# SCH_Attiny85_DevBoard_2023-10-31.net
KiCad netlist of a schematic drawn in EasyEDA
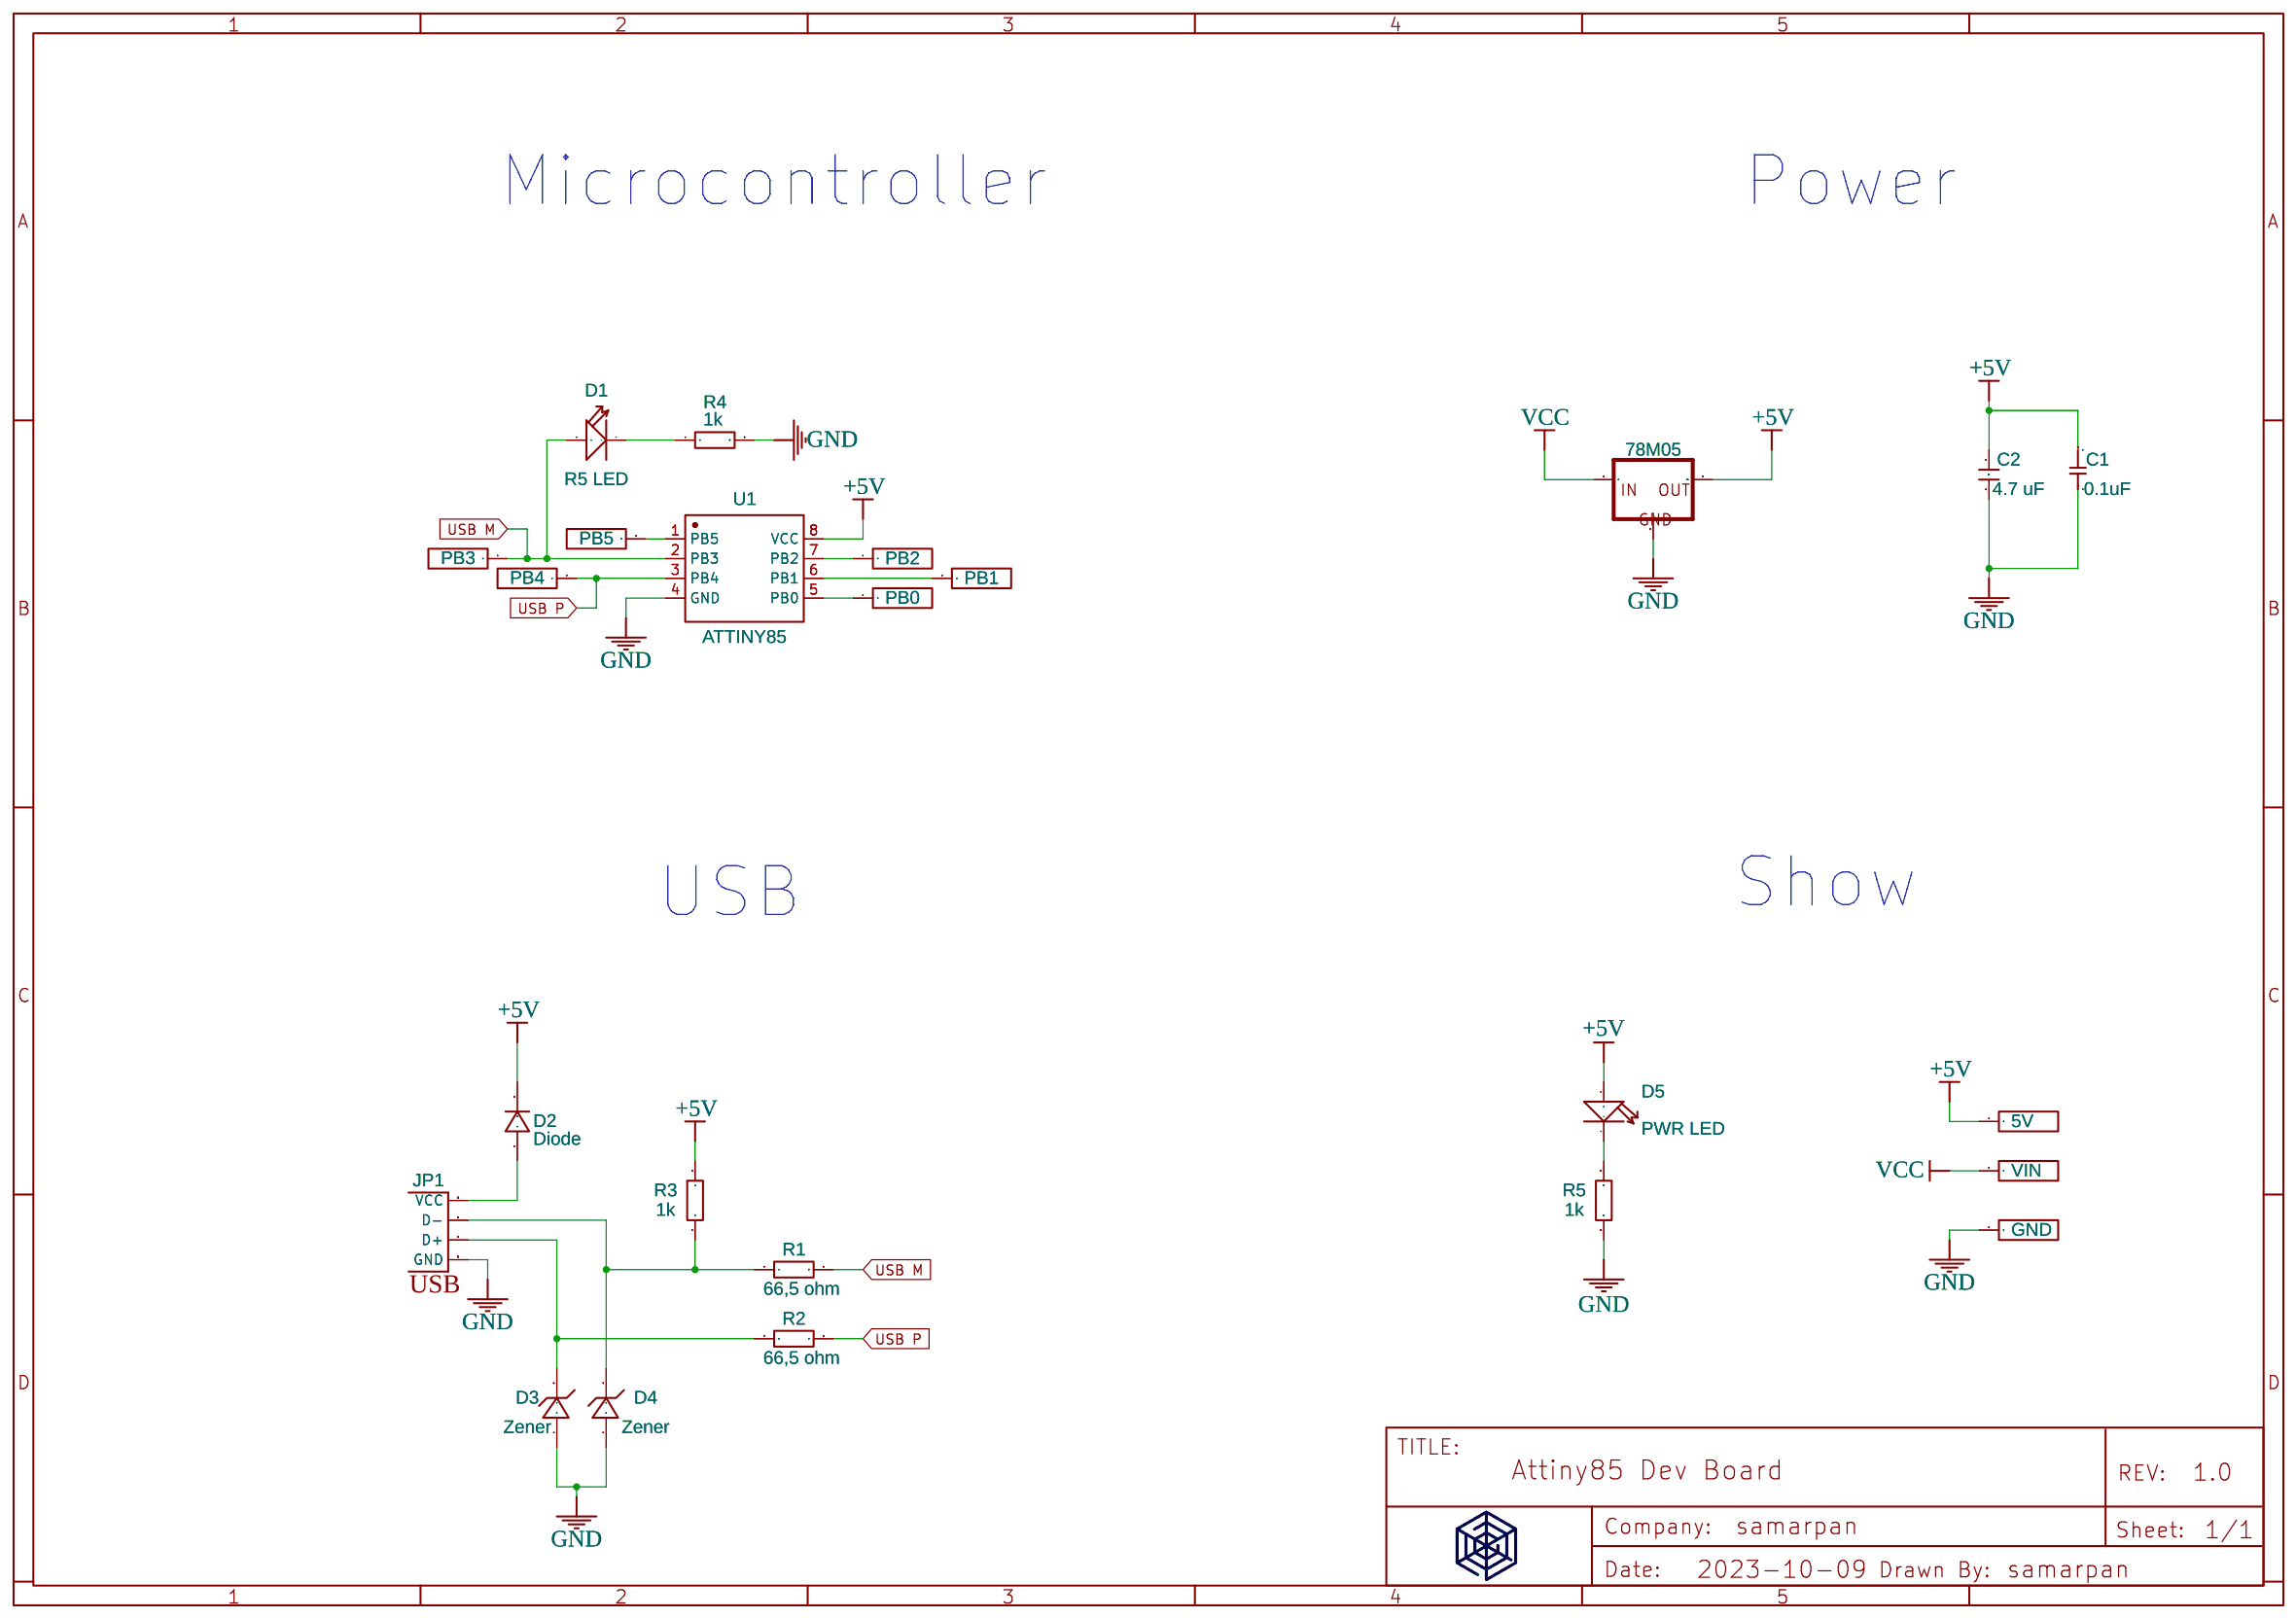
[diagram p0: schematic sheet]

(export (version "E")
  (design (tool "Eeschema 10.0.6"))
  (components
    (comp (ref "C1") (value "0.1uF") (libsource (lib "") (part "CAPNP_0402")))
    (comp (ref "C2") (value "4.7 uF") (libsource (lib "") (part "0603 Capacitor")))
    (comp (ref "D1")
      (value "R5 LED")
      (fields (field (name "Manufacturer Part") "16-219A/T2D-AR2T1QY/3T"))
      (libsource (lib "") (part "LED Green 0402_1"))
    )
    (comp (ref "D2")
      (value "Diode")
      (fields (field (name "Manufacturer Part") "Diode-1206-Y01"))
      (libsource (lib "") (part "Diode-1206-Y01"))
    )
    (comp (ref "D3")
      (value "Zener")
      (fields (field (name "Manufacturer Part") "Zener-SOD-523-Y01"))
      (libsource (lib "") (part "Zener-SOD-523-Y01"))
    )
    (comp (ref "D4")
      (value "Zener")
      (fields (field (name "Manufacturer Part") "Zener-SOD-523-Y01"))
      (libsource (lib "") (part "Zener-SOD-523-Y01"))
    )
    (comp (ref "D5")
      (value "PWR LED")
      (fields (field (name "Manufacturer Part") "16-219A/T2D-AR2T1QY/3T"))
      (libsource (lib "") (part "LED Green 0402"))
    )
    (comp (ref "H1")
      (value "PB2")
      (fields (field (name "Manufacturer Part") "MY_PIN"))
      (libsource (lib "") (part "MY_PIN_1"))
    )
    (comp (ref "H2")
      (value "PB1")
      (fields (field (name "Manufacturer Part") "MY_PIN"))
      (libsource (lib "") (part "MY_PIN_1"))
    )
    (comp (ref "H3")
      (value "PB0")
      (fields (field (name "Manufacturer Part") "MY_PIN"))
      (libsource (lib "") (part "MY_PIN_1"))
    )
    (comp (ref "H4")
      (value "PB5")
      (fields (field (name "Manufacturer Part") "MY_PIN"))
      (libsource (lib "") (part "MY_PIN"))
    )
    (comp (ref "H5")
      (value "PB3")
      (fields (field (name "Manufacturer Part") "MY_PIN"))
      (libsource (lib "") (part "MY_PIN"))
    )
    (comp (ref "H6")
      (value "PB4")
      (fields (field (name "Manufacturer Part") "MY_PIN"))
      (libsource (lib "") (part "MY_PIN"))
    )
    (comp (ref "H7")
      (value "5V")
      (fields (field (name "Manufacturer Part") "MY_PIN"))
      (libsource (lib "") (part "MY_PIN_1"))
    )
    (comp (ref "H8")
      (value "VIN")
      (fields (field (name "Manufacturer Part") "MY_PIN"))
      (libsource (lib "") (part "MY_PIN_1"))
    )
    (comp (ref "H9")
      (value "GND")
      (fields (field (name "Manufacturer Part") "MY_PIN"))
      (libsource (lib "") (part "MY_PIN_1"))
    )
    (comp (ref "JP1") (value "USB") (libsource (lib "") (part "USB_pad")))
    (comp (ref "R1")
      (value "66,5 ohm")
      (fields (field (name "Manufacturer Part") "0402WGJ0392TCE") (field (name "Manufacturer") "UniOhm"))
      (libsource (lib "") (part "0402WGJ0392TCE_C25938_1"))
    )
    (comp (ref "R2")
      (value "66,5 ohm")
      (fields (field (name "Manufacturer Part") "0402WGJ0392TCE") (field (name "Manufacturer") "UniOhm"))
      (libsource (lib "") (part "0402WGJ0392TCE_C25938_1"))
    )
    (comp (ref "R3")
      (value "1k")
      (fields (field (name "Manufacturer Part") "0402WGJ0392TCE") (field (name "Manufacturer") "UniOhm"))
      (libsource (lib "") (part "0402WGJ0392TCE_C25938"))
    )
    (comp (ref "R4")
      (value "1k")
      (fields (field (name "Manufacturer Part") "0402WGJ0392TCE") (field (name "Manufacturer") "UniOhm"))
      (libsource (lib "") (part "0402WGJ0392TCE_C25938_1"))
    )
    (comp (ref "R5")
      (value "1k")
      (fields (field (name "Manufacturer Part") "0402WGJ0392TCE") (field (name "Manufacturer") "UniOhm"))
      (libsource (lib "") (part "0402WGJ0392TCE_C25938"))
    )
    (comp (ref "U1")
      (value "ATTINY85")
      (fields
        (field (name "Manufacturer Part") "ATTINY85V-10SU")
        (field (name "Manufacturer") "Microchip Tech")
      )
      (libsource (lib "") (part "ATTINY85V-10SU"))
    )
    (comp (ref "U2") (value "78M05") (libsource (lib "") (part "78M05")))
  )
  (nets
    (net (code "1") (name "+5V") (class "Default")
      (node (ref "C1") (pin "P$1") (pinfunction "1_P$1") (pintype "bidirectional"))
      (node (ref "C2") (pin "1") (pinfunction "1_1") (pintype "unspecified"))
      (node (ref "D2") (pin "2") (pinfunction "K_2") (pintype "unspecified"))
      (node (ref "D5") (pin "+") (pinfunction "+_+") (pintype "unspecified"))
      (node (ref "H7") (pin "1") (pinfunction "1_1") (pintype "unspecified"))
      (node (ref "R3") (pin "2") (pinfunction "2_2") (pintype "input"))
      (node (ref "U1") (pin "8") (pinfunction "VCC_8") (pintype "unspecified"))
      (node (ref "U2") (pin "3") (pinfunction "OUT_3") (pintype "output"))
    )
    (net (code "2") (name "GND") (class "Default")
      (node (ref "C1") (pin "P$2") (pinfunction "2_P$2") (pintype "bidirectional"))
      (node (ref "C2") (pin "2") (pinfunction "2_2") (pintype "unspecified"))
      (node (ref "D3") (pin "1") (pinfunction "A_1") (pintype "unspecified"))
      (node (ref "D4") (pin "1") (pinfunction "A_1") (pintype "unspecified"))
      (node (ref "H9") (pin "1") (pinfunction "1_1") (pintype "unspecified"))
      (node (ref "JP1") (pin "GND") (pinfunction "GND_GND") (pintype "unspecified"))
      (node (ref "R4") (pin "2") (pinfunction "2_2") (pintype "input"))
      (node (ref "R5") (pin "1") (pinfunction "1_1") (pintype "input"))
      (node (ref "U1") (pin "4") (pinfunction "GND_4") (pintype "unspecified"))
      (node (ref "U2") (pin "2") (pinfunction "GND_2") (pintype "input"))
    )
    (net (code "3") (name "Net-(D1-Pad-)") (class "Default")
      (node (ref "D1") (pin "-") (pinfunction "-_-") (pintype "unspecified"))
      (node (ref "R4") (pin "1") (pinfunction "1_1") (pintype "input"))
    )
    (net (code "4") (name "Net-(D2-A)") (class "Default")
      (node (ref "D2") (pin "1") (pinfunction "A_1") (pintype "unspecified"))
      (node (ref "JP1") (pin "VCC") (pinfunction "VCC_VCC") (pintype "unspecified"))
    )
    (net (code "5") (name "Net-(D3-K)") (class "Default")
      (node (ref "D3") (pin "2") (pinfunction "K_2") (pintype "unspecified"))
      (node (ref "JP1") (pin "D+") (pinfunction "D+_D+") (pintype "unspecified"))
      (node (ref "R2") (pin "1") (pinfunction "1_1") (pintype "input"))
    )
    (net (code "6") (name "Net-(D4-K)") (class "Default")
      (node (ref "D4") (pin "2") (pinfunction "K_2") (pintype "unspecified"))
      (node (ref "JP1") (pin "D-") (pinfunction "D-_D-") (pintype "unspecified"))
      (node (ref "R1") (pin "1") (pinfunction "1_1") (pintype "input"))
      (node (ref "R3") (pin "1") (pinfunction "1_1") (pintype "input"))
    )
    (net (code "7") (name "Net-(D5-Pad-)") (class "Default")
      (node (ref "D5") (pin "-") (pinfunction "-_-") (pintype "unspecified"))
      (node (ref "R5") (pin "2") (pinfunction "2_2") (pintype "input"))
    )
    (net (code "8") (name "Net-(U1-PB0)") (class "Default")
      (node (ref "H3") (pin "1") (pinfunction "1_1") (pintype "unspecified"))
      (node (ref "U1") (pin "5") (pinfunction "PB0_5") (pintype "unspecified"))
    )
    (net (code "9") (name "Net-(U1-PB1)") (class "Default")
      (node (ref "H2") (pin "1") (pinfunction "1_1") (pintype "unspecified"))
      (node (ref "U1") (pin "6") (pinfunction "PB1_6") (pintype "unspecified"))
    )
    (net (code "10") (name "Net-(U1-PB2)") (class "Default")
      (node (ref "H1") (pin "1") (pinfunction "1_1") (pintype "unspecified"))
      (node (ref "U1") (pin "7") (pinfunction "PB2_7") (pintype "unspecified"))
    )
    (net (code "11") (name "Net-(U1-PB5)") (class "Default")
      (node (ref "H4") (pin "1") (pinfunction "1_1") (pintype "unspecified"))
      (node (ref "U1") (pin "1") (pinfunction "PB5_1") (pintype "unspecified"))
    )
    (net (code "12") (name "USB M") (class "Default")
      (node (ref "D1") (pin "+") (pinfunction "+_+") (pintype "unspecified"))
      (node (ref "H5") (pin "1") (pinfunction "1_1") (pintype "unspecified"))
      (node (ref "R1") (pin "2") (pinfunction "2_2") (pintype "input"))
      (node (ref "U1") (pin "2") (pinfunction "PB3_2") (pintype "unspecified"))
    )
    (net (code "13") (name "USB P") (class "Default")
      (node (ref "H6") (pin "1") (pinfunction "1_1") (pintype "unspecified"))
      (node (ref "R2") (pin "2") (pinfunction "2_2") (pintype "input"))
      (node (ref "U1") (pin "3") (pinfunction "PB4_3") (pintype "unspecified"))
    )
    (net (code "14") (name "VCC") (class "Default")
      (node (ref "H8") (pin "1") (pinfunction "1_1") (pintype "unspecified"))
      (node (ref "U2") (pin "1") (pinfunction "IN_1") (pintype "input"))
    )
  )
)
